# ESP_CAM_VVN.net
KiCad netlist of a schematic drawn in EAGLE
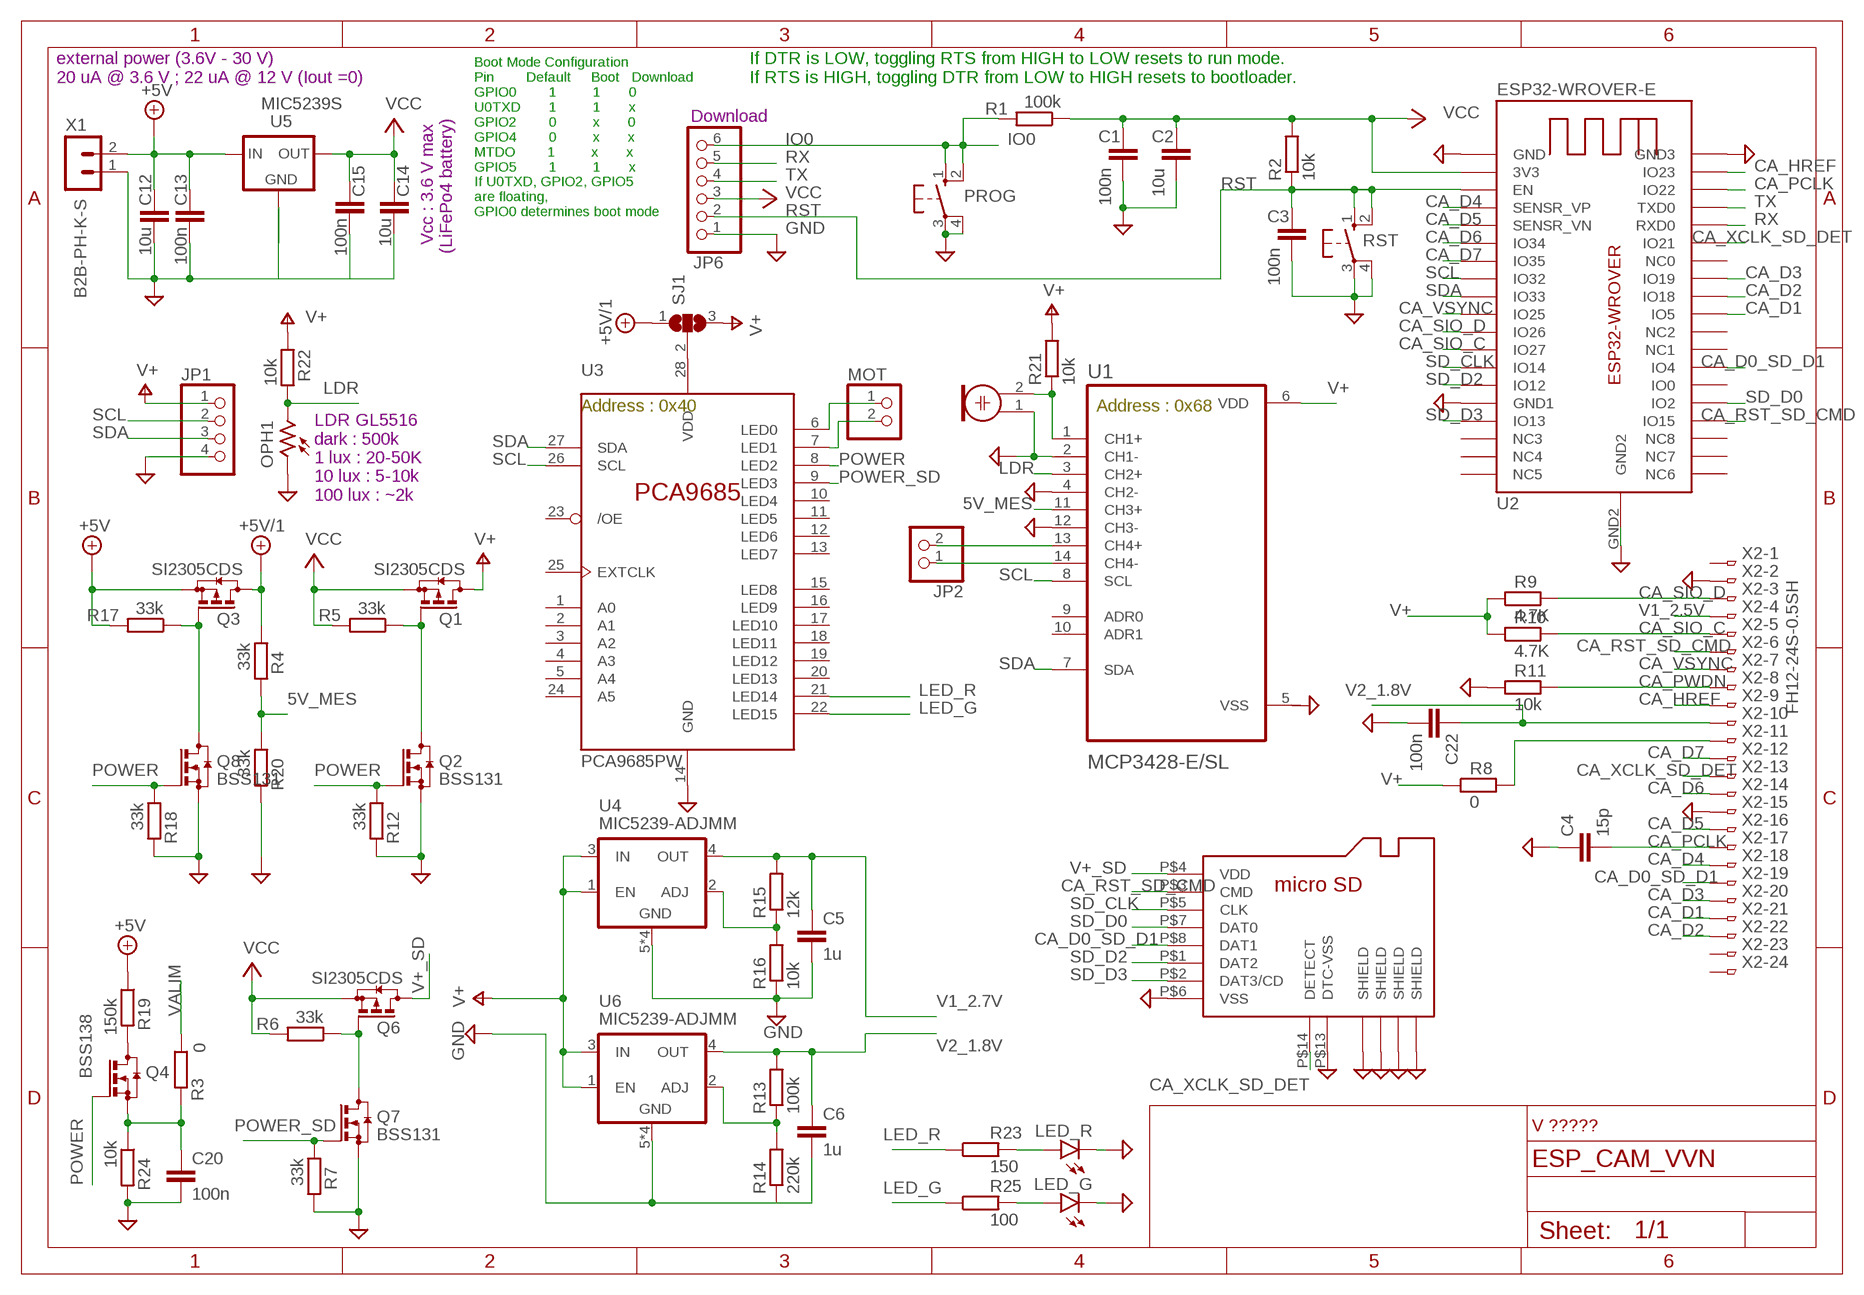
[diagram p0: schematic, sheet 1]

(export (version "E")
  (design (tool "Eeschema 10.0.6"))
  (components
    (comp (ref "C1")
      (value "100n")
      (footprint "eagle-import:C1206")
      (libsource (lib "eagle-import") (part "CC1206"))
    )
    (comp (ref "C2")
      (value "10u")
      (footprint "eagle-import:C1210")
      (libsource (lib "eagle-import") (part "CC1210"))
    )
    (comp (ref "C3")
      (value "100n")
      (footprint "eagle-import:C1206")
      (libsource (lib "eagle-import") (part "CC1206"))
    )
    (comp (ref "C4")
      (value "15p")
      (footprint "eagle-import:C1206")
      (libsource (lib "eagle-import") (part "CC1206"))
    )
    (comp (ref "C5")
      (value "1u")
      (footprint "eagle-import:C1210K")
      (libsource (lib "eagle-import") (part "C-EUC1210K"))
    )
    (comp (ref "C6")
      (value "1u")
      (footprint "eagle-import:C1210K")
      (libsource (lib "eagle-import") (part "C-EUC1210K"))
    )
    (comp (ref "C12")
      (value "10u")
      (footprint "eagle-import:C1210")
      (libsource (lib "eagle-import") (part "CC1210"))
    )
    (comp (ref "C13")
      (value "100n")
      (footprint "eagle-import:C1206")
      (libsource (lib "eagle-import") (part "CC1206"))
    )
    (comp (ref "C14")
      (value "10u")
      (footprint "eagle-import:C1210")
      (libsource (lib "eagle-import") (part "CC1210"))
    )
    (comp (ref "C15")
      (value "100n")
      (footprint "eagle-import:C1206")
      (libsource (lib "eagle-import") (part "CC1206"))
    )
    (comp (ref "C20")
      (value "100n")
      (footprint "eagle-import:C1206")
      (libsource (lib "eagle-import") (part "CC1206"))
    )
    (comp (ref "C22")
      (value "100n")
      (footprint "eagle-import:C1206")
      (libsource (lib "eagle-import") (part "CC1206"))
    )
    (comp (ref "JP1")
      (value "PINHD-1X4")
      (footprint "eagle-import:1X04")
      (libsource (lib "eagle-import") (part "PINHD-1X4"))
    )
    (comp (ref "JP2")
      (value "PINHD-1X2")
      (footprint "eagle-import:1X02")
      (libsource (lib "eagle-import") (part "PINHD-1X2"))
    )
    (comp (ref "JP6")
      (value "PINHD-1X6")
      (footprint "eagle-import:1X06")
      (libsource (lib "eagle-import") (part "PINHD-1X6"))
    )
    (comp (ref "LED_G")
      (value "LEDSMT1206")
      (footprint "eagle-import:1206")
      (libsource (lib "eagle-import") (part "LEDSMT1206"))
    )
    (comp (ref "LED_R")
      (value "LEDSMT1206")
      (footprint "eagle-import:1206")
      (libsource (lib "eagle-import") (part "LEDSMT1206"))
    )
    (comp (ref "M1")
      (value "ELECTRET_MICROPHON-WM-62PC/62PK")
      (footprint "eagle-import:WM-62PC_62PK")
      (libsource (lib "eagle-import") (part "ELECTRET_MICROPHON-WM-62PC/62PK"))
    )
    (comp (ref "MOT")
      (value "PINHD-1X2")
      (footprint "eagle-import:1X02")
      (libsource (lib "eagle-import") (part "PINHD-1X2"))
    )
    (comp (ref "OPH1")
      (value "VT93N2")
      (footprint "eagle-import:VT900")
      (libsource (lib "eagle-import") (part "VT93N2"))
    )
    (comp (ref "PROG")
      (value "10-XX")
      (footprint "eagle-import:B3F-10XX")
      (fields (field (name "MPN") "B3F-1000"))
      (libsource (lib "eagle-import") (part "10-XX"))
    )
    (comp (ref "Q1")
      (value "SI2305CDS")
      (footprint "eagle-import:SOT23")
      (libsource (lib "eagle-import") (part "SI2305CDS"))
    )
    (comp (ref "Q2")
      (value "BSS131")
      (footprint "eagle-import:SOT23")
      (libsource (lib "eagle-import") (part "BSS131"))
    )
    (comp (ref "Q3")
      (value "SI2305CDS")
      (footprint "eagle-import:SOT23")
      (libsource (lib "eagle-import") (part "SI2305CDS"))
    )
    (comp (ref "Q4")
      (value "BSS138")
      (footprint "eagle-import:SOT23")
      (libsource (lib "eagle-import") (part "BSS138"))
    )
    (comp (ref "Q6")
      (value "SI2305CDS")
      (footprint "eagle-import:SOT23")
      (libsource (lib "eagle-import") (part "SI2305CDS"))
    )
    (comp (ref "Q7")
      (value "BSS131")
      (footprint "eagle-import:SOT23")
      (libsource (lib "eagle-import") (part "BSS131"))
    )
    (comp (ref "Q8")
      (value "BSS131")
      (footprint "eagle-import:SOT23")
      (libsource (lib "eagle-import") (part "BSS131"))
    )
    (comp (ref "R1")
      (value "100k")
      (footprint "eagle-import:R1206")
      (libsource (lib "eagle-import") (part "RR1206"))
    )
    (comp (ref "R2")
      (value "10k")
      (footprint "eagle-import:R1206")
      (libsource (lib "eagle-import") (part "RR1206"))
    )
    (comp (ref "R3")
      (value "0")
      (footprint "eagle-import:R1206")
      (libsource (lib "eagle-import") (part "RR1206"))
    )
    (comp (ref "R4")
      (value "33k")
      (footprint "eagle-import:R1206")
      (libsource (lib "eagle-import") (part "RR1206"))
    )
    (comp (ref "R5")
      (value "33k")
      (footprint "eagle-import:R1206")
      (libsource (lib "eagle-import") (part "RR1206"))
    )
    (comp (ref "R6")
      (value "33k")
      (footprint "eagle-import:R1206")
      (libsource (lib "eagle-import") (part "RR1206"))
    )
    (comp (ref "R7")
      (value "33k")
      (footprint "eagle-import:R1206")
      (libsource (lib "eagle-import") (part "RR1206"))
    )
    (comp (ref "R8")
      (value "0")
      (footprint "eagle-import:R1206")
      (libsource (lib "eagle-import") (part "RR1206"))
    )
    (comp (ref "R9")
      (value "4.7K")
      (footprint "eagle-import:R1206")
      (libsource (lib "eagle-import") (part "RR1206"))
    )
    (comp (ref "R10")
      (value "4.7K")
      (footprint "eagle-import:R1206")
      (libsource (lib "eagle-import") (part "RR1206"))
    )
    (comp (ref "R11")
      (value "10k")
      (footprint "eagle-import:R1206")
      (libsource (lib "eagle-import") (part "RR1206"))
    )
    (comp (ref "R12")
      (value "33k")
      (footprint "eagle-import:R1206")
      (libsource (lib "eagle-import") (part "RR1206"))
    )
    (comp (ref "R13")
      (value "100k")
      (footprint "eagle-import:R1206")
      (libsource (lib "eagle-import") (part "R-EU_R1206"))
    )
    (comp (ref "R14")
      (value "220k")
      (footprint "eagle-import:R1206")
      (libsource (lib "eagle-import") (part "R-EU_R1206"))
    )
    (comp (ref "R15")
      (value "12k")
      (footprint "eagle-import:R1206")
      (libsource (lib "eagle-import") (part "R-EU_R1206"))
    )
    (comp (ref "R16")
      (value "10k")
      (footprint "eagle-import:R1206")
      (libsource (lib "eagle-import") (part "R-EU_R1206"))
    )
    (comp (ref "R17")
      (value "33k")
      (footprint "eagle-import:R1206")
      (libsource (lib "eagle-import") (part "RR1206"))
    )
    (comp (ref "R18")
      (value "33k")
      (footprint "eagle-import:R1206")
      (libsource (lib "eagle-import") (part "RR1206"))
    )
    (comp (ref "R19")
      (value "150k")
      (footprint "eagle-import:R1206")
      (libsource (lib "eagle-import") (part "RR1206"))
    )
    (comp (ref "R20")
      (value "33k")
      (footprint "eagle-import:R1206")
      (libsource (lib "eagle-import") (part "RR1206"))
    )
    (comp (ref "R21")
      (value "10k")
      (footprint "eagle-import:R1206")
      (libsource (lib "eagle-import") (part "RR1206"))
    )
    (comp (ref "R22")
      (value "10k")
      (footprint "eagle-import:R1206")
      (libsource (lib "eagle-import") (part "RR1206"))
    )
    (comp (ref "R23")
      (value "150")
      (footprint "eagle-import:R1206")
      (libsource (lib "eagle-import") (part "RR1206"))
    )
    (comp (ref "R24")
      (value "10k")
      (footprint "eagle-import:R1206")
      (libsource (lib "eagle-import") (part "RR1206"))
    )
    (comp (ref "R25")
      (value "100")
      (footprint "eagle-import:R1206")
      (libsource (lib "eagle-import") (part "RR1206"))
    )
    (comp (ref "RST")
      (value "10-XX")
      (footprint "eagle-import:B3F-10XX")
      (fields (field (name "MPN") "B3F-1000"))
      (libsource (lib "eagle-import") (part "10-XX"))
    )
    (comp (ref "SD1")
      (value "MICRO-SD-8")
      (footprint "eagle-import:MICROSDMOLEX")
      (libsource (lib "eagle-import") (part "MICRO-SD-8"))
    )
    (comp (ref "SJ1")
      (value "SJ2W")
      (footprint "eagle-import:SJ_2")
      (libsource (lib "eagle-import") (part "SJ2W"))
    )
    (comp (ref "U1")
      (value "MCP3428-E/SL")
      (footprint "eagle-import:SOIC127P600X175-14N")
      (fields (field (name "MF") "Microchip"))
      (libsource (lib "eagle-import") (part "MCP3428-E/SL"))
    )
    (comp (ref "U2")
      (value "ESP32-WROVER-E")
      (footprint "eagle-import:ESP32-WROVER")
      (libsource (lib "eagle-import") (part "ESP32-WROVER-E"))
    )
    (comp (ref "U3")
      (value "PCA9685PW")
      (footprint "eagle-import:TSSOP28")
      (libsource (lib "eagle-import") (part "PCA9685PW"))
    )
    (comp (ref "U4")
      (value "MIC5239-ADJMM")
      (footprint "eagle-import:MSOP08")
      (libsource (lib "eagle-import") (part "MIC5239-ADJMM"))
    )
    (comp (ref "U5")
      (value "MIC5239S")
      (footprint "eagle-import:SOT223")
      (libsource (lib "eagle-import") (part "MIC5239S"))
    )
    (comp (ref "U6")
      (value "MIC5239-ADJMM")
      (footprint "eagle-import:MSOP08")
      (libsource (lib "eagle-import") (part "MIC5239-ADJMM"))
    )
    (comp (ref "X1")
      (value "B2B-PH-K-S")
      (footprint "eagle-import:B2B-PH-K-S")
      (libsource (lib "eagle-import") (part "B2B-PH-K-S"))
    )
    (comp (ref "X2")
      (value "FH12-24S-0.5SH")
      (footprint "eagle-import:FH12-24S-0.5SH")
      (fields (field (name "MPN") "FH12-24S-0.5SH(55)"))
      (libsource (lib "eagle-import") (part "FH12-24S-0.5SH"))
    )
  )
  (nets
    (net (code "1") (name "+5V") (class "Default")
      (node (ref "C12") (pin "1") (pinfunction "1_1") (pintype "passive"))
      (node (ref "C13") (pin "1") (pinfunction "1_1") (pintype "passive"))
      (node (ref "Q3") (pin "2") (pinfunction "S_2") (pintype "passive"))
      (node (ref "R17") (pin "2") (pinfunction "2_2") (pintype "passive"))
      (node (ref "R19") (pin "1") (pinfunction "1_1") (pintype "passive"))
      (node (ref "U5") (pin "1") (pinfunction "IN_1") (pintype "input"))
      (node (ref "X1") (pin "2") (pinfunction "2_2") (pintype "passive"))
    )
    (net (code "2") (name "+5V{slash}1") (class "Default")
      (node (ref "Q3") (pin "3") (pinfunction "D_3") (pintype "passive"))
      (node (ref "R4") (pin "1") (pinfunction "1_1") (pintype "passive"))
      (node (ref "SJ1") (pin "1") (pinfunction "1_1") (pintype "passive"))
    )
    (net (code "3") (name "/5V_MES") (class "Default")
      (node (ref "R20") (pin "1") (pinfunction "1_1") (pintype "passive"))
      (node (ref "R4") (pin "2") (pinfunction "2_2") (pintype "passive"))
      (node (ref "U1") (pin "11") (pinfunction "CH3+_11") (pintype "input"))
    )
    (net (code "4") (name "/CA_D0_SD_D1") (class "Default")
      (node (ref "SD1") (pin "P$8") (pinfunction "DAT1_P$8") (pintype "bidirectional"))
      (node (ref "U2") (pin "IO4") (pinfunction "IO4_IO4") (pintype "bidirectional"))
      (node (ref "X2") (pin "19") (pinfunction "1_19") (pintype "passive"))
    )
    (net (code "5") (name "/CA_D1") (class "Default")
      (node (ref "U2") (pin "IO5") (pinfunction "IO5_IO5") (pintype "bidirectional"))
      (node (ref "X2") (pin "21") (pinfunction "1_21") (pintype "passive"))
    )
    (net (code "6") (name "/CA_D2") (class "Default")
      (node (ref "U2") (pin "IO18") (pinfunction "IO18_IO18") (pintype "bidirectional"))
      (node (ref "X2") (pin "22") (pinfunction "1_22") (pintype "passive"))
    )
    (net (code "7") (name "/CA_D3") (class "Default")
      (node (ref "U2") (pin "IO19") (pinfunction "IO19_IO19") (pintype "bidirectional"))
      (node (ref "X2") (pin "20") (pinfunction "1_20") (pintype "passive"))
    )
    (net (code "8") (name "/CA_D4") (class "Default")
      (node (ref "U2") (pin "SENSOR_VP") (pinfunction "SENSR_VP_SENSOR_VP") (pintype "bidirectional"))
      (node (ref "X2") (pin "18") (pinfunction "1_18") (pintype "passive"))
    )
    (net (code "9") (name "/CA_D5") (class "Default")
      (node (ref "U2") (pin "SENSOR_VN") (pinfunction "SENSR_VN_SENSOR_VN") (pintype "bidirectional"))
      (node (ref "X2") (pin "16") (pinfunction "1_16") (pintype "passive"))
    )
    (net (code "10") (name "/CA_D6") (class "Default")
      (node (ref "U2") (pin "IO34") (pinfunction "IO34_IO34") (pintype "bidirectional"))
      (node (ref "X2") (pin "14") (pinfunction "1_14") (pintype "passive"))
    )
    (net (code "11") (name "/CA_D7") (class "Default")
      (node (ref "U2") (pin "IO35") (pinfunction "IO35_IO35") (pintype "bidirectional"))
      (node (ref "X2") (pin "12") (pinfunction "1_12") (pintype "passive"))
    )
    (net (code "12") (name "/CA_HREF") (class "Default")
      (node (ref "U2") (pin "IO23") (pinfunction "IO23_IO23") (pintype "bidirectional"))
      (node (ref "X2") (pin "9") (pinfunction "1_9") (pintype "passive"))
    )
    (net (code "13") (name "/CA_PCLK") (class "Default")
      (node (ref "C4") (pin "2") (pinfunction "2_2") (pintype "passive"))
      (node (ref "U2") (pin "IO22") (pinfunction "IO22_IO22") (pintype "bidirectional"))
      (node (ref "X2") (pin "17") (pinfunction "1_17") (pintype "passive"))
    )
    (net (code "14") (name "/CA_PWDN") (class "Default")
      (node (ref "R11") (pin "2") (pinfunction "2_2") (pintype "passive"))
      (node (ref "X2") (pin "8") (pinfunction "1_8") (pintype "passive"))
    )
    (net (code "15") (name "/CA_RST_SD_CMD") (class "Default")
      (node (ref "SD1") (pin "P$3") (pinfunction "CMD_P$3") (pintype "bidirectional"))
      (node (ref "U2") (pin "IO15") (pinfunction "IO15_IO15") (pintype "bidirectional"))
      (node (ref "X2") (pin "6") (pinfunction "1_6") (pintype "passive"))
    )
    (net (code "16") (name "/CA_SIO_C") (class "Default")
      (node (ref "R10") (pin "2") (pinfunction "2_2") (pintype "passive"))
      (node (ref "U2") (pin "IO27") (pinfunction "IO27_IO27") (pintype "bidirectional"))
      (node (ref "X2") (pin "5") (pinfunction "1_5") (pintype "passive"))
    )
    (net (code "17") (name "/CA_SIO_D") (class "Default")
      (node (ref "R9") (pin "2") (pinfunction "2_2") (pintype "passive"))
      (node (ref "U2") (pin "IO26") (pinfunction "IO26_IO26") (pintype "bidirectional"))
      (node (ref "X2") (pin "3") (pinfunction "1_3") (pintype "passive"))
    )
    (net (code "18") (name "/CA_VSYNC") (class "Default")
      (node (ref "U2") (pin "IO25") (pinfunction "IO25_IO25") (pintype "bidirectional"))
      (node (ref "X2") (pin "7") (pinfunction "1_7") (pintype "passive"))
    )
    (net (code "19") (name "/CA_XCLK_SD_DET") (class "Default")
      (node (ref "SD1") (pin "P$14") (pinfunction "DETECT_P$14") (pintype "power_in"))
      (node (ref "U2") (pin "IO21") (pinfunction "IO21_IO21") (pintype "bidirectional"))
      (node (ref "X2") (pin "13") (pinfunction "1_13") (pintype "passive"))
    )
    (net (code "20") (name "/IO0") (class "Default")
      (node (ref "JP6") (pin "6") (pinfunction "6_6") (pintype "passive"))
      (node (ref "PROG") (pin "1") (pinfunction "S_1") (pintype "passive"))
      (node (ref "PROG") (pin "2") (pinfunction "S1_2") (pintype "passive"))
      (node (ref "R1") (pin "2") (pinfunction "2_2") (pintype "passive"))
    )
    (net (code "21") (name "/LDR") (class "Default")
      (node (ref "OPH1") (pin "2") (pinfunction "2_2") (pintype "passive"))
      (node (ref "R22") (pin "2") (pinfunction "2_2") (pintype "passive"))
      (node (ref "U1") (pin "3") (pinfunction "CH2+_3") (pintype "input"))
    )
    (net (code "22") (name "/LED_G") (class "Default")
      (node (ref "R25") (pin "1") (pinfunction "1_1") (pintype "passive"))
      (node (ref "U3") (pin "22") (pinfunction "LED15_22") (pintype "bidirectional"))
    )
    (net (code "23") (name "/LED_R") (class "Default")
      (node (ref "R23") (pin "1") (pinfunction "1_1") (pintype "passive"))
      (node (ref "U3") (pin "21") (pinfunction "LED14_21") (pintype "bidirectional"))
    )
    (net (code "24") (name "/POWER") (class "Default")
      (node (ref "Q2") (pin "1") (pinfunction "G_1") (pintype "passive"))
      (node (ref "Q4") (pin "1") (pinfunction "G_1") (pintype "passive"))
      (node (ref "Q8") (pin "1") (pinfunction "G_1") (pintype "passive"))
      (node (ref "R12") (pin "1") (pinfunction "1_1") (pintype "passive"))
      (node (ref "R18") (pin "1") (pinfunction "1_1") (pintype "passive"))
      (node (ref "U3") (pin "8") (pinfunction "LED2_8") (pintype "bidirectional"))
    )
    (net (code "25") (name "/POWER_SD") (class "Default")
      (node (ref "Q7") (pin "1") (pinfunction "G_1") (pintype "passive"))
      (node (ref "R7") (pin "1") (pinfunction "1_1") (pintype "passive"))
      (node (ref "U3") (pin "9") (pinfunction "LED3_9") (pintype "bidirectional"))
    )
    (net (code "26") (name "/RST") (class "Default")
      (node (ref "C3") (pin "1") (pinfunction "1_1") (pintype "passive"))
      (node (ref "JP6") (pin "2") (pinfunction "2_2") (pintype "passive"))
      (node (ref "R2") (pin "1") (pinfunction "1_1") (pintype "passive"))
      (node (ref "RST") (pin "1") (pinfunction "S_1") (pintype "passive"))
      (node (ref "RST") (pin "2") (pinfunction "S1_2") (pintype "passive"))
      (node (ref "U2") (pin "EN") (pinfunction "EN_EN") (pintype "bidirectional"))
    )
    (net (code "27") (name "/RX") (class "Default")
      (node (ref "JP6") (pin "5") (pinfunction "5_5") (pintype "passive"))
      (node (ref "U2") (pin "RXD0") (pinfunction "RXD0_RXD0") (pintype "bidirectional"))
    )
    (net (code "28") (name "/SCL") (class "Default")
      (node (ref "JP1") (pin "2") (pinfunction "2_2") (pintype "passive"))
      (node (ref "U1") (pin "8") (pinfunction "SCL_8") (pintype "input"))
      (node (ref "U2") (pin "IO32") (pinfunction "IO32_IO32") (pintype "bidirectional"))
      (node (ref "U3") (pin "26") (pinfunction "SCL_26") (pintype "bidirectional"))
    )
    (net (code "29") (name "/SDA") (class "Default")
      (node (ref "JP1") (pin "3") (pinfunction "3_3") (pintype "passive"))
      (node (ref "U1") (pin "7") (pinfunction "SDA_7") (pintype "bidirectional"))
      (node (ref "U2") (pin "IO33") (pinfunction "IO33_IO33") (pintype "bidirectional"))
      (node (ref "U3") (pin "27") (pinfunction "SDA_27") (pintype "bidirectional"))
    )
    (net (code "30") (name "/SD_CLK") (class "Default")
      (node (ref "SD1") (pin "P$5") (pinfunction "CLK_P$5") (pintype "bidirectional"))
      (node (ref "U2") (pin "IO14") (pinfunction "IO14_IO14") (pintype "bidirectional"))
    )
    (net (code "31") (name "/SD_D0") (class "Default")
      (node (ref "SD1") (pin "P$7") (pinfunction "DAT0_P$7") (pintype "bidirectional"))
      (node (ref "U2") (pin "IO2") (pinfunction "IO2_IO2") (pintype "bidirectional"))
    )
    (net (code "32") (name "/SD_D2") (class "Default")
      (node (ref "SD1") (pin "P$1") (pinfunction "DAT2_P$1") (pintype "bidirectional"))
      (node (ref "U2") (pin "IO12") (pinfunction "IO12_IO12") (pintype "bidirectional"))
    )
    (net (code "33") (name "/SD_D3") (class "Default")
      (node (ref "SD1") (pin "P$2") (pinfunction "DAT3/CD_P$2") (pintype "bidirectional"))
      (node (ref "U2") (pin "IO13") (pinfunction "IO13_IO13") (pintype "bidirectional"))
    )
    (net (code "34") (name "/TX") (class "Default")
      (node (ref "JP6") (pin "4") (pinfunction "4_4") (pintype "passive"))
      (node (ref "U2") (pin "TXD0") (pinfunction "TXD0_TXD0") (pintype "bidirectional"))
    )
    (net (code "35") (name "/V+_SD") (class "Default")
      (node (ref "Q6") (pin "3") (pinfunction "D_3") (pintype "passive"))
      (node (ref "SD1") (pin "P$4") (pinfunction "VDD_P$4") (pintype "power_in"))
    )
    (net (code "36") (name "/V1_2.5V") (class "Default")
      (node (ref "X2") (pin "4") (pinfunction "1_4") (pintype "passive"))
    )
    (net (code "37") (name "/V1_2.7V") (class "Default")
      (node (ref "C5") (pin "1") (pinfunction "1_1") (pintype "passive"))
      (node (ref "R15") (pin "2") (pinfunction "2_2") (pintype "passive"))
      (node (ref "U4") (pin "4") (pinfunction "OUT_4") (pintype "passive"))
    )
    (net (code "38") (name "/V2_1.8V") (class "Default")
      (node (ref "C22") (pin "1") (pinfunction "1_1") (pintype "passive"))
      (node (ref "C6") (pin "1") (pinfunction "1_1") (pintype "passive"))
      (node (ref "R13") (pin "2") (pinfunction "2_2") (pintype "passive"))
      (node (ref "U6") (pin "4") (pinfunction "OUT_4") (pintype "passive"))
      (node (ref "X2") (pin "10") (pinfunction "1_10") (pintype "passive"))
    )
    (net (code "39") (name "/VALIM") (class "Default")
      (node (ref "R3") (pin "1") (pinfunction "1_1") (pintype "passive"))
    )
    (net (code "40") (name "/VSS") (class "Default")
      (node (ref "U1") (pin "5") (pinfunction "VSS_5") (pintype "power_in"))
    )
    (net (code "41") (name "GND") (class "Default")
      (node (ref "C1") (pin "2") (pinfunction "2_2") (pintype "passive"))
      (node (ref "C12") (pin "2") (pinfunction "2_2") (pintype "passive"))
      (node (ref "C13") (pin "2") (pinfunction "2_2") (pintype "passive"))
      (node (ref "C14") (pin "2") (pinfunction "2_2") (pintype "passive"))
      (node (ref "C15") (pin "2") (pinfunction "2_2") (pintype "passive"))
      (node (ref "C2") (pin "2") (pinfunction "2_2") (pintype "passive"))
      (node (ref "C20") (pin "2") (pinfunction "2_2") (pintype "passive"))
      (node (ref "C22") (pin "2") (pinfunction "2_2") (pintype "passive"))
      (node (ref "C3") (pin "2") (pinfunction "2_2") (pintype "passive"))
      (node (ref "C4") (pin "1") (pinfunction "1_1") (pintype "passive"))
      (node (ref "C5") (pin "2") (pinfunction "2_2") (pintype "passive"))
      (node (ref "C6") (pin "2") (pinfunction "2_2") (pintype "passive"))
      (node (ref "JP1") (pin "4") (pinfunction "4_4") (pintype "passive"))
      (node (ref "JP6") (pin "1") (pinfunction "1_1") (pintype "passive"))
      (node (ref "LED_G") (pin "C") (pinfunction "C_C") (pintype "passive"))
      (node (ref "LED_R") (pin "C") (pinfunction "C_C") (pintype "passive"))
      (node (ref "M1") (pin "1") (pinfunction "1_1") (pintype "passive"))
      (node (ref "OPH1") (pin "1") (pinfunction "1_1") (pintype "passive"))
      (node (ref "PROG") (pin "3") (pinfunction "P_3") (pintype "passive"))
      (node (ref "PROG") (pin "4") (pinfunction "P1_4") (pintype "passive"))
      (node (ref "Q2") (pin "2") (pinfunction "S_2") (pintype "passive"))
      (node (ref "Q7") (pin "2") (pinfunction "S_2") (pintype "passive"))
      (node (ref "Q8") (pin "2") (pinfunction "S_2") (pintype "passive"))
      (node (ref "R11") (pin "1") (pinfunction "1_1") (pintype "passive"))
      (node (ref "R12") (pin "2") (pinfunction "2_2") (pintype "passive"))
      (node (ref "R14") (pin "1") (pinfunction "1_1") (pintype "passive"))
      (node (ref "R16") (pin "1") (pinfunction "1_1") (pintype "passive"))
      (node (ref "R18") (pin "2") (pinfunction "2_2") (pintype "passive"))
      (node (ref "R20") (pin "2") (pinfunction "2_2") (pintype "passive"))
      (node (ref "R24") (pin "2") (pinfunction "2_2") (pintype "passive"))
      (node (ref "R7") (pin "2") (pinfunction "2_2") (pintype "passive"))
      (node (ref "RST") (pin "3") (pinfunction "P_3") (pintype "passive"))
      (node (ref "RST") (pin "4") (pinfunction "P1_4") (pintype "passive"))
      (node (ref "SD1") (pin "P$10") (pinfunction "SHIELD_P$10") (pintype "power_in"))
      (node (ref "SD1") (pin "P$11") (pinfunction "SHIELD_P$11") (pintype "power_in"))
      (node (ref "SD1") (pin "P$12") (pinfunction "SHIELD_P$12") (pintype "power_in"))
      (node (ref "SD1") (pin "P$13") (pinfunction "DTC-VSS_P$13") (pintype "power_in"))
      (node (ref "SD1") (pin "P$6") (pinfunction "VSS_P$6") (pintype "power_in"))
      (node (ref "SD1") (pin "P$9") (pinfunction "SHIELD_P$9") (pintype "power_in"))
      (node (ref "U1") (pin "12") (pinfunction "CH3-_12") (pintype "input"))
      (node (ref "U1") (pin "2") (pinfunction "CH1-_2") (pintype "input"))
      (node (ref "U1") (pin "4") (pinfunction "CH2-_4") (pintype "input"))
      (node (ref "U2") (pin "GND") (pinfunction "GND_GND") (pintype "bidirectional"))
      (node (ref "U2") (pin "GND1") (pinfunction "GND1_GND1") (pintype "bidirectional"))
      (node (ref "U2") (pin "GND2") (pinfunction "GND2_GND2") (pintype "bidirectional"))
      (node (ref "U2") (pin "GND3") (pinfunction "GND3_GND3") (pintype "bidirectional"))
      (node (ref "U3") (pin "14") (pinfunction "GND_14") (pintype "power_in"))
      (node (ref "U4") (pin "5") (pinfunction "GND_5") (pintype "power_in"))
      (node (ref "U4") (pin "6") (pinfunction "GND_6") (pintype "power_in"))
      (node (ref "U4") (pin "7") (pinfunction "GND_7") (pintype "power_in"))
      (node (ref "U4") (pin "8") (pinfunction "GND_8") (pintype "power_in"))
      (node (ref "U5") (pin "2") (pinfunction "GND_2") (pintype "passive"))
      (node (ref "U5") (pin "4") (pinfunction "GND_4") (pintype "passive"))
      (node (ref "U6") (pin "5") (pinfunction "GND_5") (pintype "power_in"))
      (node (ref "U6") (pin "6") (pinfunction "GND_6") (pintype "power_in"))
      (node (ref "U6") (pin "7") (pinfunction "GND_7") (pintype "power_in"))
      (node (ref "U6") (pin "8") (pinfunction "GND_8") (pintype "power_in"))
      (node (ref "X1") (pin "1") (pinfunction "1_1") (pintype "passive"))
      (node (ref "X2") (pin "15") (pinfunction "1_15") (pintype "passive"))
      (node (ref "X2") (pin "2") (pinfunction "1_2") (pintype "passive"))
    )
    (net (code "42") (name "Net-(LED_G-PadA)") (class "Default")
      (node (ref "LED_G") (pin "A") (pinfunction "A_A") (pintype "passive"))
      (node (ref "R25") (pin "2") (pinfunction "2_2") (pintype "passive"))
    )
    (net (code "43") (name "Net-(LED_R-PadA)") (class "Default")
      (node (ref "LED_R") (pin "A") (pinfunction "A_A") (pintype "passive"))
      (node (ref "R23") (pin "2") (pinfunction "2_2") (pintype "passive"))
    )
    (net (code "44") (name "Net-(Q1-G)") (class "Default")
      (node (ref "Q1") (pin "1") (pinfunction "G_1") (pintype "passive"))
      (node (ref "Q2") (pin "3") (pinfunction "D_3") (pintype "passive"))
      (node (ref "R5") (pin "1") (pinfunction "1_1") (pintype "passive"))
    )
    (net (code "45") (name "Net-(Q3-G)") (class "Default")
      (node (ref "Q3") (pin "1") (pinfunction "G_1") (pintype "passive"))
      (node (ref "Q8") (pin "3") (pinfunction "D_3") (pintype "passive"))
      (node (ref "R17") (pin "1") (pinfunction "1_1") (pintype "passive"))
    )
    (net (code "46") (name "Net-(Q4-D)") (class "Default")
      (node (ref "Q4") (pin "3") (pinfunction "D_3") (pintype "passive"))
      (node (ref "R19") (pin "2") (pinfunction "2_2") (pintype "passive"))
    )
    (net (code "47") (name "Net-(Q4-S)") (class "Default")
      (node (ref "C20") (pin "1") (pinfunction "1_1") (pintype "passive"))
      (node (ref "Q4") (pin "2") (pinfunction "S_2") (pintype "passive"))
      (node (ref "R24") (pin "1") (pinfunction "1_1") (pintype "passive"))
      (node (ref "R3") (pin "2") (pinfunction "2_2") (pintype "passive"))
    )
    (net (code "48") (name "Net-(Q6-G)") (class "Default")
      (node (ref "Q6") (pin "1") (pinfunction "G_1") (pintype "passive"))
      (node (ref "Q7") (pin "3") (pinfunction "D_3") (pintype "passive"))
      (node (ref "R6") (pin "1") (pinfunction "1_1") (pintype "passive"))
    )
    (net (code "49") (name "Net-(U1-CH1+)") (class "Default")
      (node (ref "M1") (pin "2") (pinfunction "2_2") (pintype "passive"))
      (node (ref "R21") (pin "1") (pinfunction "1_1") (pintype "passive"))
      (node (ref "U1") (pin "1") (pinfunction "CH1+_1") (pintype "input"))
    )
    (net (code "50") (name "Net-(U1-CH4+)") (class "Default")
      (node (ref "JP2") (pin "2") (pinfunction "2_2") (pintype "passive"))
      (node (ref "U1") (pin "13") (pinfunction "CH4+_13") (pintype "input"))
    )
    (net (code "51") (name "Net-(U1-CH4-)") (class "Default")
      (node (ref "JP2") (pin "1") (pinfunction "1_1") (pintype "passive"))
      (node (ref "U1") (pin "14") (pinfunction "CH4-_14") (pintype "input"))
    )
    (net (code "52") (name "Net-(U3-LED0)") (class "Default")
      (node (ref "MOT") (pin "1") (pinfunction "1_1") (pintype "passive"))
      (node (ref "U3") (pin "6") (pinfunction "LED0_6") (pintype "bidirectional"))
    )
    (net (code "53") (name "Net-(U3-LED1)") (class "Default")
      (node (ref "MOT") (pin "2") (pinfunction "2_2") (pintype "passive"))
      (node (ref "U3") (pin "7") (pinfunction "LED1_7") (pintype "bidirectional"))
    )
    (net (code "54") (name "Net-(U3-VDD)") (class "Default")
      (node (ref "SJ1") (pin "2") (pinfunction "2_2") (pintype "passive"))
      (node (ref "U3") (pin "28") (pinfunction "VDD_28") (pintype "power_in"))
    )
    (net (code "55") (name "Net-(U4-ADJ)") (class "Default")
      (node (ref "R15") (pin "1") (pinfunction "1_1") (pintype "passive"))
      (node (ref "R16") (pin "2") (pinfunction "2_2") (pintype "passive"))
      (node (ref "U4") (pin "2") (pinfunction "ADJ_2") (pintype "passive"))
    )
    (net (code "56") (name "Net-(U6-ADJ)") (class "Default")
      (node (ref "R13") (pin "1") (pinfunction "1_1") (pintype "passive"))
      (node (ref "R14") (pin "2") (pinfunction "2_2") (pintype "passive"))
      (node (ref "U6") (pin "2") (pinfunction "ADJ_2") (pintype "passive"))
    )
    (net (code "57") (name "Net-(X2C-1)") (class "Default")
      (node (ref "R8") (pin "2") (pinfunction "2_2") (pintype "passive"))
      (node (ref "X2") (pin "11") (pinfunction "1_11") (pintype "passive"))
    )
    (net (code "58") (name "V+") (class "Default")
      (node (ref "JP1") (pin "1") (pinfunction "1_1") (pintype "passive"))
      (node (ref "Q1") (pin "3") (pinfunction "D_3") (pintype "passive"))
      (node (ref "R10") (pin "1") (pinfunction "1_1") (pintype "passive"))
      (node (ref "R21") (pin "2") (pinfunction "2_2") (pintype "passive"))
      (node (ref "R22") (pin "1") (pinfunction "1_1") (pintype "passive"))
      (node (ref "R8") (pin "1") (pinfunction "1_1") (pintype "passive"))
      (node (ref "R9") (pin "1") (pinfunction "1_1") (pintype "passive"))
      (node (ref "SJ1") (pin "3") (pinfunction "3_3") (pintype "passive"))
      (node (ref "U1") (pin "6") (pinfunction "VDD_6") (pintype "power_in"))
      (node (ref "U4") (pin "1") (pinfunction "EN_1") (pintype "input"))
      (node (ref "U4") (pin "3") (pinfunction "IN_3") (pintype "input"))
      (node (ref "U6") (pin "1") (pinfunction "EN_1") (pintype "input"))
      (node (ref "U6") (pin "3") (pinfunction "IN_3") (pintype "input"))
    )
    (net (code "59") (name "VCC") (class "Default")
      (node (ref "C1") (pin "1") (pinfunction "1_1") (pintype "passive"))
      (node (ref "C14") (pin "1") (pinfunction "1_1") (pintype "passive"))
      (node (ref "C15") (pin "1") (pinfunction "1_1") (pintype "passive"))
      (node (ref "C2") (pin "1") (pinfunction "1_1") (pintype "passive"))
      (node (ref "JP6") (pin "3") (pinfunction "3_3") (pintype "passive"))
      (node (ref "Q1") (pin "2") (pinfunction "S_2") (pintype "passive"))
      (node (ref "Q6") (pin "2") (pinfunction "S_2") (pintype "passive"))
      (node (ref "R1") (pin "1") (pinfunction "1_1") (pintype "passive"))
      (node (ref "R2") (pin "2") (pinfunction "2_2") (pintype "passive"))
      (node (ref "R5") (pin "2") (pinfunction "2_2") (pintype "passive"))
      (node (ref "R6") (pin "2") (pinfunction "2_2") (pintype "passive"))
      (node (ref "U2") (pin "VDD33") (pinfunction "3V3_VDD33") (pintype "bidirectional"))
      (node (ref "U5") (pin "3") (pinfunction "OUT_3") (pintype "passive"))
    )
    (net (code "60") (name "unconnected-(U1-ADR0-Pad9)") (class "Default")
      (node (ref "U1") (pin "9") (pinfunction "ADR0_9") (pintype "bidirectional"))
    )
    (net (code "61") (name "unconnected-(U1-ADR1-Pad10)") (class "Default")
      (node (ref "U1") (pin "10") (pinfunction "ADR1_10") (pintype "bidirectional"))
    )
    (net (code "62") (name "unconnected-(U2-NC3-PadCLK)") (class "Default")
      (node (ref "U2") (pin "CLK") (pinfunction "NC3_CLK") (pintype "bidirectional"))
    )
    (net (code "63") (name "unconnected-(U2-NC4-PadCMD)") (class "Default")
      (node (ref "U2") (pin "CMD") (pinfunction "NC4_CMD") (pintype "bidirectional"))
    )
    (net (code "64") (name "unconnected-(U2-NC5-PadSD0)") (class "Default")
      (node (ref "U2") (pin "SD0") (pinfunction "NC5_SD0") (pintype "bidirectional"))
    )
    (net (code "65") (name "unconnected-(U2-NC6-PadSD1)") (class "Default")
      (node (ref "U2") (pin "SD1") (pinfunction "NC6_SD1") (pintype "bidirectional"))
    )
    (net (code "66") (name "unconnected-(U2-NC7-PadSD2)") (class "Default")
      (node (ref "U2") (pin "SD2") (pinfunction "NC7_SD2") (pintype "bidirectional"))
    )
    (net (code "67") (name "unconnected-(U2-NC8-PadSD3)") (class "Default")
      (node (ref "U2") (pin "SD3") (pinfunction "NC8_SD3") (pintype "bidirectional"))
    )
    (net (code "68") (name "unconnected-(U2-PadIO0)") (class "Default")
      (node (ref "U2") (pin "IO0") (pinfunction "IO0_IO0") (pintype "bidirectional"))
    )
    (net (code "69") (name "unconnected-(U2-PadNC0)") (class "Default")
      (node (ref "U2") (pin "NC0") (pinfunction "NC0_NC0") (pintype "bidirectional"))
    )
    (net (code "70") (name "unconnected-(U2-PadNC1)") (class "Default")
      (node (ref "U2") (pin "NC1") (pinfunction "NC1_NC1") (pintype "bidirectional"))
    )
    (net (code "71") (name "unconnected-(U2-PadNC2)") (class "Default")
      (node (ref "U2") (pin "NC2") (pinfunction "NC2_NC2") (pintype "bidirectional"))
    )
    (net (code "72") (name "unconnected-(U3-A0-Pad1)") (class "Default")
      (node (ref "U3") (pin "1") (pinfunction "A0_1") (pintype "bidirectional"))
    )
    (net (code "73") (name "unconnected-(U3-A1-Pad2)") (class "Default")
      (node (ref "U3") (pin "2") (pinfunction "A1_2") (pintype "bidirectional"))
    )
    (net (code "74") (name "unconnected-(U3-A2-Pad3)") (class "Default")
      (node (ref "U3") (pin "3") (pinfunction "A2_3") (pintype "bidirectional"))
    )
    (net (code "75") (name "unconnected-(U3-A3-Pad4)") (class "Default")
      (node (ref "U3") (pin "4") (pinfunction "A3_4") (pintype "bidirectional"))
    )
    (net (code "76") (name "unconnected-(U3-A4-Pad5)") (class "Default")
      (node (ref "U3") (pin "5") (pinfunction "A4_5") (pintype "bidirectional"))
    )
    (net (code "77") (name "unconnected-(U3-A5-Pad24)") (class "Default")
      (node (ref "U3") (pin "24") (pinfunction "A5_24") (pintype "bidirectional"))
    )
    (net (code "78") (name "unconnected-(U3-EXTCLK-Pad25)") (class "Default")
      (node (ref "U3") (pin "25") (pinfunction "EXTCLK_25") (pintype "input"))
    )
    (net (code "79") (name "unconnected-(U3-LED4-Pad10)") (class "Default")
      (node (ref "U3") (pin "10") (pinfunction "LED4_10") (pintype "bidirectional"))
    )
    (net (code "80") (name "unconnected-(U3-LED5-Pad11)") (class "Default")
      (node (ref "U3") (pin "11") (pinfunction "LED5_11") (pintype "bidirectional"))
    )
    (net (code "81") (name "unconnected-(U3-LED6-Pad12)") (class "Default")
      (node (ref "U3") (pin "12") (pinfunction "LED6_12") (pintype "bidirectional"))
    )
    (net (code "82") (name "unconnected-(U3-LED7-Pad13)") (class "Default")
      (node (ref "U3") (pin "13") (pinfunction "LED7_13") (pintype "bidirectional"))
    )
    (net (code "83") (name "unconnected-(U3-LED8-Pad15)") (class "Default")
      (node (ref "U3") (pin "15") (pinfunction "LED8_15") (pintype "bidirectional"))
    )
    (net (code "84") (name "unconnected-(U3-LED9-Pad16)") (class "Default")
      (node (ref "U3") (pin "16") (pinfunction "LED9_16") (pintype "bidirectional"))
    )
    (net (code "85") (name "unconnected-(U3-LED10-Pad17)") (class "Default")
      (node (ref "U3") (pin "17") (pinfunction "LED10_17") (pintype "bidirectional"))
    )
    (net (code "86") (name "unconnected-(U3-LED11-Pad18)") (class "Default")
      (node (ref "U3") (pin "18") (pinfunction "LED11_18") (pintype "bidirectional"))
    )
    (net (code "87") (name "unconnected-(U3-LED12-Pad19)") (class "Default")
      (node (ref "U3") (pin "19") (pinfunction "LED12_19") (pintype "bidirectional"))
    )
    (net (code "88") (name "unconnected-(U3-LED13-Pad20)") (class "Default")
      (node (ref "U3") (pin "20") (pinfunction "LED13_20") (pintype "bidirectional"))
    )
    (net (code "89") (name "unconnected-(U3-{slash}OE-Pad23)") (class "Default")
      (node (ref "U3") (pin "23") (pinfunction "/OE_23") (pintype "bidirectional"))
    )
    (net (code "90") (name "unconnected-(X2-Pad1)") (class "Default")
      (node (ref "X2") (pin "1") (pinfunction "1_1") (pintype "passive"))
    )
    (net (code "91") (name "unconnected-(X2P-1-Pad23)") (class "Default")
      (node (ref "X2") (pin "23") (pinfunction "1_23") (pintype "passive"))
    )
    (net (code "92") (name "unconnected-(X2Q-1-Pad24)") (class "Default")
      (node (ref "X2") (pin "24") (pinfunction "1_24") (pintype "passive"))
    )
  )
)
